# pwm_audio.net
KiCad netlist of a schematic drawn in EAGLE
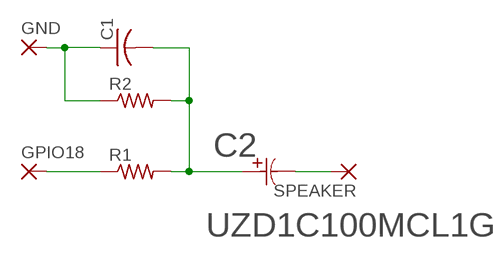
[diagram p0: schematic, sheet 1]

(export (version "E")
  (design (tool "Eeschema 10.0.6"))
  (components
    (comp (ref "C1")
      (value "C-USC1206")
      (footprint "eagle-import:C1206")
      (libsource (lib "eagle-import") (part "C-USC1206"))
    )
    (comp (ref "C2")
      (value "UZD1C100MCL1GB")
      (footprint "eagle-import:PCAP_5X3-ELECT")
      (fields (field (name "COPYRIGHT") "Copyright (C) 2015 Accelerated Designs. All rights reserved"))
      (libsource (lib "eagle-import") (part "UZD1C100MCL1GB"))
    )
    (comp (ref "GND")
      (value "2,54/1,0")
      (footprint "eagle-import:2,54_1,0")
      (libsource (lib "eagle-import") (part "2,54/1,0"))
    )
    (comp (ref "GPIO18")
      (value "2,54/1,0")
      (footprint "eagle-import:2,54_1,0")
      (libsource (lib "eagle-import") (part "2,54/1,0"))
    )
    (comp (ref "R1")
      (value "R-US_R1206")
      (footprint "eagle-import:R1206")
      (libsource (lib "eagle-import") (part "R-US_R1206"))
    )
    (comp (ref "R2")
      (value "R-US_R1206")
      (footprint "eagle-import:R1206")
      (libsource (lib "eagle-import") (part "R-US_R1206"))
    )
    (comp (ref "SPEAKER")
      (value "2,54/1,0")
      (footprint "eagle-import:2,54_1,0")
      (libsource (lib "eagle-import") (part "2,54/1,0"))
    )
  )
  (nets
    (net (code "1") (name "Net-(C2-11)") (class "Default")
      (node (ref "C1") (pin "2") (pinfunction "2_2") (pintype "passive"))
      (node (ref "C2") (pin "1") (pinfunction "11_1") (pintype "passive"))
      (node (ref "R1") (pin "2") (pinfunction "2_2") (pintype "passive"))
      (node (ref "R2") (pin "2") (pinfunction "2_2") (pintype "passive"))
    )
    (net (code "2") (name "Net-(C2-22)") (class "Default")
      (node (ref "C2") (pin "2") (pinfunction "22_2") (pintype "passive"))
      (node (ref "SPEAKER") (pin "1") (pinfunction "P_1") (pintype "passive"))
    )
    (net (code "3") (name "Net-(GND-P)") (class "Default")
      (node (ref "C1") (pin "1") (pinfunction "1_1") (pintype "passive"))
      (node (ref "GND") (pin "1") (pinfunction "P_1") (pintype "passive"))
      (node (ref "R2") (pin "1") (pinfunction "1_1") (pintype "passive"))
    )
    (net (code "4") (name "Net-(GPIO18-P)") (class "Default")
      (node (ref "GPIO18") (pin "1") (pinfunction "P_1") (pintype "passive"))
      (node (ref "R1") (pin "1") (pinfunction "1_1") (pintype "passive"))
    )
  )
)
